# childboard_dht22_v1.net
KiCad netlist of a schematic drawn in EAGLE
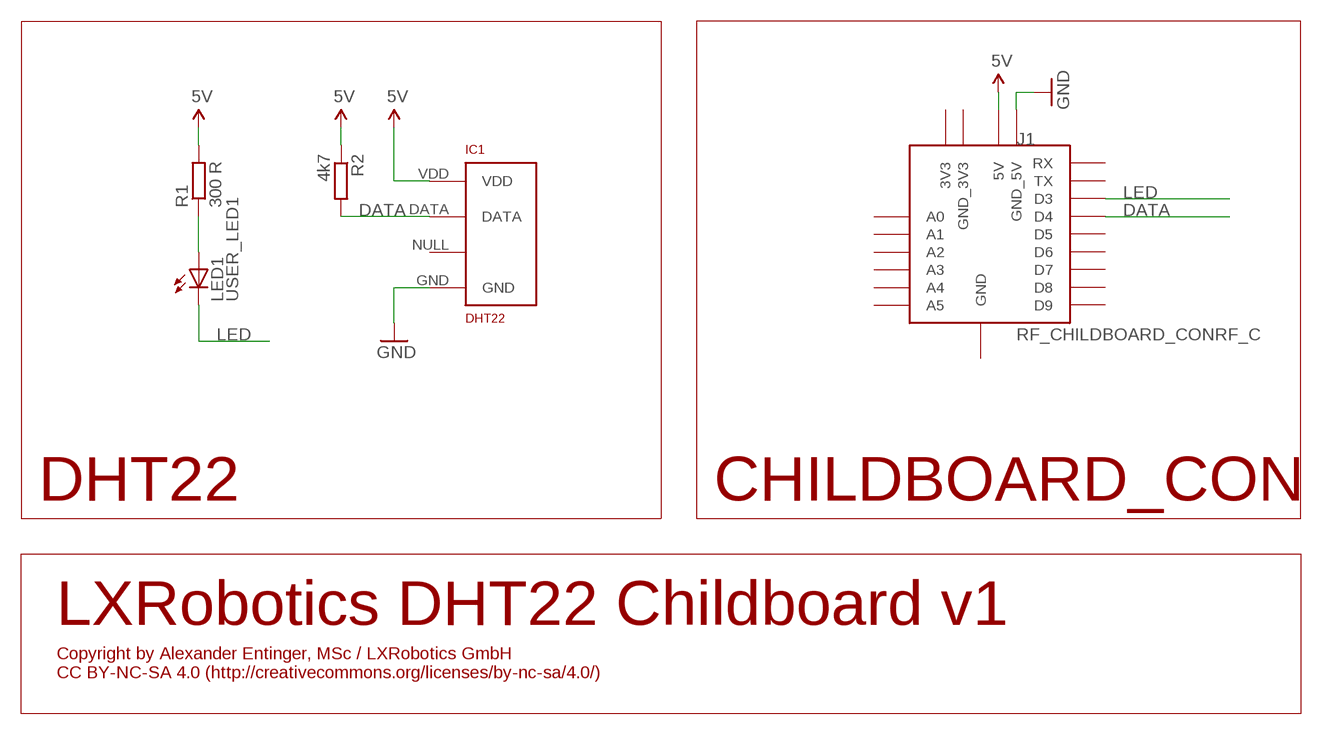
[diagram p0: schematic, sheet 1]

(export (version "E")
  (design (tool "Eeschema 10.0.6"))
  (components
    (comp (ref "IC1")
      (value "DHT22")
      (footprint "eagle-import:RHT03_DHT-22_RA")
      (libsource (lib "eagle-import") (part "RHT03_DHT-22_AM2302RA"))
    )
    (comp (ref "J1")
      (value "RF_CHILDBOARD_CONRF_C")
      (footprint "eagle-import:RF_CHILDBOARD_CON")
      (libsource (lib "eagle-import") (part "RF_CHILDBOARD_CONRF_C"))
    )
    (comp (ref "LED1")
      (value "USER_LED1")
      (footprint "eagle-import:LED5MM")
      (libsource (lib "eagle-import") (part "LED5MM"))
    )
    (comp (ref "R1")
      (value "300 R")
      (footprint "eagle-import:0204_7")
      (libsource (lib "eagle-import") (part "R-EU_0204/7"))
    )
    (comp (ref "R2")
      (value "4k7")
      (footprint "eagle-import:0204_7")
      (libsource (lib "eagle-import") (part "R-EU_0204/7"))
    )
  )
  (nets
    (net (code "1") (name "/DATA") (class "Default")
      (node (ref "IC1") (pin "DATA") (pinfunction "DATA_DATA") (pintype "bidirectional"))
      (node (ref "J1") (pin "D4") (pinfunction "D4_D4") (pintype "bidirectional"))
      (node (ref "R2") (pin "2") (pinfunction "2_2") (pintype "passive"))
    )
    (net (code "2") (name "/LED") (class "Default")
      (node (ref "J1") (pin "D3") (pinfunction "D3_D3") (pintype "bidirectional"))
      (node (ref "LED1") (pin "K") (pinfunction "C_K") (pintype "passive"))
    )
    (net (code "3") (name "5V") (class "Default")
      (node (ref "IC1") (pin "VDD") (pinfunction "VDD_VDD") (pintype "power_in"))
      (node (ref "J1") (pin "5V") (pinfunction "5V_5V") (pintype "bidirectional"))
      (node (ref "R1") (pin "2") (pinfunction "2_2") (pintype "passive"))
      (node (ref "R2") (pin "1") (pinfunction "1_1") (pintype "passive"))
    )
    (net (code "4") (name "GND") (class "Default")
      (node (ref "IC1") (pin "GND") (pinfunction "GND_GND") (pintype "power_in"))
      (node (ref "J1") (pin "GND_5V") (pinfunction "GND_5V_GND_5V") (pintype "bidirectional"))
    )
    (net (code "5") (name "Net-(LED1-PadA)") (class "Default")
      (node (ref "LED1") (pin "A") (pinfunction "A_A") (pintype "passive"))
      (node (ref "R1") (pin "1") (pinfunction "1_1") (pintype "passive"))
    )
    (net (code "6") (name "unconnected-(IC1-PadNULL)") (class "Default")
      (node (ref "IC1") (pin "NULL") (pinfunction "NULL_NULL") (pintype "no_connect"))
    )
    (net (code "7") (name "unconnected-(J1-GND-PadGND_)") (class "Default")
      (node (ref "J1") (pin "GND_") (pinfunction "GND_GND_") (pintype "bidirectional"))
    )
    (net (code "8") (name "unconnected-(J1-Pad3V3)") (class "Default")
      (node (ref "J1") (pin "3V3") (pinfunction "3V3_3V3") (pintype "bidirectional"))
    )
    (net (code "9") (name "unconnected-(J1-PadA0)") (class "Default")
      (node (ref "J1") (pin "A0") (pinfunction "A0_A0") (pintype "bidirectional"))
    )
    (net (code "10") (name "unconnected-(J1-PadA1)") (class "Default")
      (node (ref "J1") (pin "A1") (pinfunction "A1_A1") (pintype "bidirectional"))
    )
    (net (code "11") (name "unconnected-(J1-PadA2)") (class "Default")
      (node (ref "J1") (pin "A2") (pinfunction "A2_A2") (pintype "bidirectional"))
    )
    (net (code "12") (name "unconnected-(J1-PadA3)") (class "Default")
      (node (ref "J1") (pin "A3") (pinfunction "A3_A3") (pintype "bidirectional"))
    )
    (net (code "13") (name "unconnected-(J1-PadA4)") (class "Default")
      (node (ref "J1") (pin "A4") (pinfunction "A4_A4") (pintype "bidirectional"))
    )
    (net (code "14") (name "unconnected-(J1-PadA5)") (class "Default")
      (node (ref "J1") (pin "A5") (pinfunction "A5_A5") (pintype "bidirectional"))
    )
    (net (code "15") (name "unconnected-(J1-PadD5)") (class "Default")
      (node (ref "J1") (pin "D5") (pinfunction "D5_D5") (pintype "bidirectional"))
    )
    (net (code "16") (name "unconnected-(J1-PadD6)") (class "Default")
      (node (ref "J1") (pin "D6") (pinfunction "D6_D6") (pintype "bidirectional"))
    )
    (net (code "17") (name "unconnected-(J1-PadD7)") (class "Default")
      (node (ref "J1") (pin "D7") (pinfunction "D7_D7") (pintype "bidirectional"))
    )
    (net (code "18") (name "unconnected-(J1-PadD8)") (class "Default")
      (node (ref "J1") (pin "D8") (pinfunction "D8_D8") (pintype "bidirectional"))
    )
    (net (code "19") (name "unconnected-(J1-PadD9)") (class "Default")
      (node (ref "J1") (pin "D9") (pinfunction "D9_D9") (pintype "bidirectional"))
    )
    (net (code "20") (name "unconnected-(J1-PadGND_3V3)") (class "Default")
      (node (ref "J1") (pin "GND_3V3") (pinfunction "GND_3V3_GND_3V3") (pintype "bidirectional"))
    )
    (net (code "21") (name "unconnected-(J1-PadRX)") (class "Default")
      (node (ref "J1") (pin "RX") (pinfunction "RX_RX") (pintype "bidirectional"))
    )
    (net (code "22") (name "unconnected-(J1-PadTX)") (class "Default")
      (node (ref "J1") (pin "TX") (pinfunction "TX_TX") (pintype "bidirectional"))
    )
  )
)
